# sonic_beacon.net
KiCad netlist of a schematic drawn in EAGLE
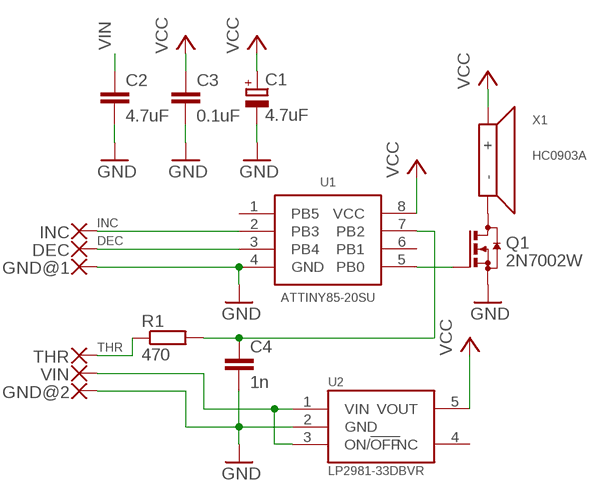
[diagram p0: schematic, sheet 1]

(export (version "E")
  (design (tool "Eeschema 10.0.6"))
  (components
    (comp (ref "C1")
      (value "4.7uF")
      (footprint "eagle-import:A_3216-18W")
      (libsource (lib "eagle-import") (part "C_TANT"))
    )
    (comp (ref "C2")
      (value "4.7uF")
      (footprint "eagle-import:C0805K")
      (libsource (lib "eagle-import") (part "C_CER"))
    )
    (comp (ref "C3")
      (value "0.1uF")
      (footprint "eagle-import:C0805K")
      (libsource (lib "eagle-import") (part "C_CER"))
    )
    (comp (ref "C4")
      (value "1n")
      (footprint "eagle-import:C0805K")
      (libsource (lib "eagle-import") (part "C_CER"))
    )
    (comp (ref "DEC")
      (value "WIREPAD")
      (footprint "eagle-import:PAD")
      (libsource (lib "eagle-import") (part "WIREPAD"))
    )
    (comp (ref "GND@1")
      (value "WIREPAD")
      (footprint "eagle-import:PAD")
      (libsource (lib "eagle-import") (part "WIREPAD"))
    )
    (comp (ref "GND@2")
      (value "WIREPAD")
      (footprint "eagle-import:PAD")
      (libsource (lib "eagle-import") (part "WIREPAD"))
    )
    (comp (ref "INC")
      (value "WIREPAD")
      (footprint "eagle-import:PAD")
      (libsource (lib "eagle-import") (part "WIREPAD"))
    )
    (comp (ref "Q1")
      (value "2N7002W")
      (footprint "eagle-import:SC-70")
      (libsource (lib "eagle-import") (part "2N7002W"))
    )
    (comp (ref "R1")
      (value "470")
      (footprint "eagle-import:R0805W")
      (libsource (lib "eagle-import") (part "R"))
    )
    (comp (ref "THR")
      (value "WIREPAD")
      (footprint "eagle-import:PAD")
      (libsource (lib "eagle-import") (part "WIREPAD"))
    )
    (comp (ref "U1")
      (value "ATTINY85-20SU")
      (footprint "eagle-import:8S2")
      (libsource (lib "eagle-import") (part "ATTINY85-20SU"))
    )
    (comp (ref "U2")
      (value "LP2981-33DBVR")
      (footprint "eagle-import:SOT-23")
      (libsource (lib "eagle-import") (part "LP2981-33DBVR"))
    )
    (comp (ref "VIN")
      (value "WIREPAD")
      (footprint "eagle-import:PAD")
      (libsource (lib "eagle-import") (part "WIREPAD"))
    )
    (comp (ref "X1")
      (value "HC0903A")
      (footprint "eagle-import:HC0903A")
      (libsource (lib "eagle-import") (part "HC0903A"))
    )
  )
  (nets
    (net (code "1") (name "/DEC") (class "Default")
      (node (ref "DEC") (pin "P$1") (pinfunction "P_P$1") (pintype "passive"))
      (node (ref "U1") (pin "3") (pinfunction "PB4_3") (pintype "bidirectional"))
    )
    (net (code "2") (name "/INC") (class "Default")
      (node (ref "INC") (pin "P$1") (pinfunction "P_P$1") (pintype "passive"))
      (node (ref "U1") (pin "2") (pinfunction "PB3_2") (pintype "bidirectional"))
    )
    (net (code "3") (name "/THR") (class "Default")
      (node (ref "R1") (pin "1") (pinfunction "1_1") (pintype "passive"))
      (node (ref "THR") (pin "P$1") (pinfunction "P_P$1") (pintype "passive"))
    )
    (net (code "4") (name "/VIN") (class "Default")
      (node (ref "C2") (pin "1") (pinfunction "1_1") (pintype "passive"))
    )
    (net (code "5") (name "GND") (class "Default")
      (node (ref "C1") (pin "-") (pinfunction "-_-") (pintype "passive"))
      (node (ref "C2") (pin "2") (pinfunction "2_2") (pintype "passive"))
      (node (ref "C3") (pin "2") (pinfunction "2_2") (pintype "passive"))
      (node (ref "C4") (pin "2") (pinfunction "2_2") (pintype "passive"))
      (node (ref "GND@1") (pin "P$1") (pinfunction "P_P$1") (pintype "passive"))
      (node (ref "GND@2") (pin "P$1") (pinfunction "P_P$1") (pintype "passive"))
      (node (ref "Q1") (pin "2") (pinfunction "S_2") (pintype "passive"))
      (node (ref "U1") (pin "4") (pinfunction "GND_4") (pintype "bidirectional"))
      (node (ref "U2") (pin "2") (pinfunction "GND_2") (pintype "bidirectional"))
    )
    (net (code "6") (name "Net-(Q1-D)") (class "Default")
      (node (ref "Q1") (pin "3") (pinfunction "D_3") (pintype "passive"))
      (node (ref "X1") (pin "2") (pinfunction "-_2") (pintype "bidirectional"))
    )
    (net (code "7") (name "Net-(Q1-G)") (class "Default")
      (node (ref "Q1") (pin "1") (pinfunction "G_1") (pintype "passive"))
      (node (ref "U1") (pin "5") (pinfunction "PB0_5") (pintype "bidirectional"))
    )
    (net (code "8") (name "Net-(U1-PB2)") (class "Default")
      (node (ref "C4") (pin "1") (pinfunction "1_1") (pintype "passive"))
      (node (ref "R1") (pin "2") (pinfunction "2_2") (pintype "passive"))
      (node (ref "U1") (pin "7") (pinfunction "PB2_7") (pintype "bidirectional"))
    )
    (net (code "9") (name "Net-(U2-ON{slash}~{OFF})") (class "Default")
      (node (ref "U2") (pin "1") (pinfunction "VIN_1") (pintype "bidirectional"))
      (node (ref "U2") (pin "3") (pinfunction "ON/~{OFF}_3") (pintype "bidirectional"))
      (node (ref "VIN") (pin "P$1") (pinfunction "P_P$1") (pintype "passive"))
    )
    (net (code "10") (name "VCC") (class "Default")
      (node (ref "C1") (pin "+") (pinfunction "+_+") (pintype "passive"))
      (node (ref "C3") (pin "1") (pinfunction "1_1") (pintype "passive"))
      (node (ref "U1") (pin "8") (pinfunction "VCC_8") (pintype "bidirectional"))
      (node (ref "U2") (pin "5") (pinfunction "VOUT_5") (pintype "bidirectional"))
      (node (ref "X1") (pin "1") (pinfunction "+_1") (pintype "bidirectional"))
    )
    (net (code "11") (name "unconnected-(U1-PB1-Pad6)") (class "Default")
      (node (ref "U1") (pin "6") (pinfunction "PB1_6") (pintype "bidirectional"))
    )
    (net (code "12") (name "unconnected-(U1-PB5-Pad1)") (class "Default")
      (node (ref "U1") (pin "1") (pinfunction "PB5_1") (pintype "bidirectional"))
    )
    (net (code "13") (name "unconnected-(U2-NC-Pad4)") (class "Default")
      (node (ref "U2") (pin "4") (pinfunction "NC_4") (pintype "bidirectional"))
    )
  )
)
